# KNoT_Thing_Starter_Board.net
KiCad netlist of a schematic drawn in Altium Designer
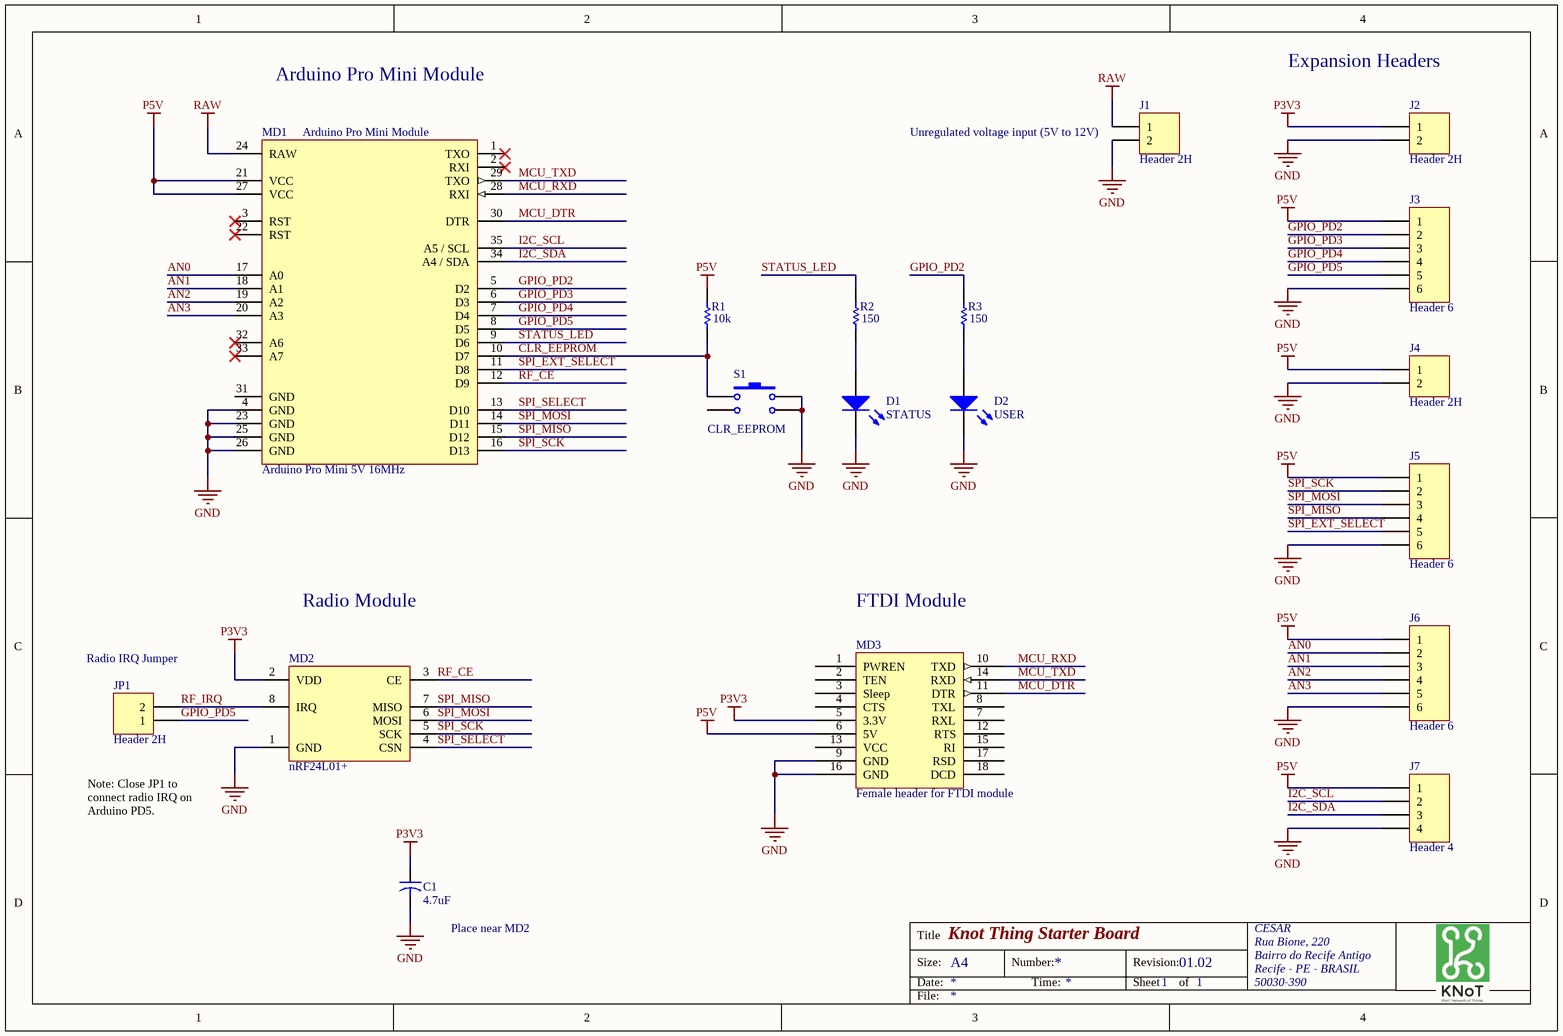
[diagram p0: KNoT_Thing_Starter_Board.SchDoc]

(export (version "E")
  (design (tool "Eeschema 10.0.6"))
  (components
    (comp (ref "C1")
      (value "4.7uF")
      (footprint "CAP RADIAL 5mm")
      (description "Capacitor Radial 4.7µF")
      (fields (field (name "Comment") "CAPC_RADIAL_100") (field (name "PUBLISHER") "Altium Limited"))
      (libsource (lib "KNoT_Thing") (part "CAPC1608L_1"))
    )
    (comp (ref "D1")
      (value "STATUS")
      (footprint "LED")
      (description "Typical RED, GREEN, YELLOW, AMBER GaAs LED")
      (fields (field (name "PUBLISHER") "Altium Limited"))
      (libsource (lib "KNoT_Thing") (part "LED"))
    )
    (comp (ref "D2")
      (value "USER")
      (footprint "LED")
      (description "Typical RED, GREEN, YELLOW, AMBER GaAs LED")
      (fields (field (name "PUBLISHER") "Altium Limited"))
      (libsource (lib "KNoT_Thing") (part "LED"))
    )
    (comp (ref "J1")
      (value "Header 2H")
      (footprint "HDR1X2")
      (description "Header, 2-Pin, Right Angle")
      (fields (field (name "PUBLISHER") "Altium Limited"))
      (libsource (lib "KNoT_Thing") (part "Header 2H"))
    )
    (comp (ref "J2")
      (value "Header 2H")
      (footprint "HDR1X2")
      (description "Header, 2-Pin, Right Angle")
      (fields (field (name "PUBLISHER") "Altium Limited"))
      (libsource (lib "KNoT_Thing") (part "Header 2H"))
    )
    (comp (ref "J3")
      (value "Header 6")
      (footprint "HDR1X6")
      (description "Header, 6-Pin")
      (fields (field (name "PUBLISHER") "Altium Limited"))
      (libsource (lib "KNoT_Thing") (part "Header 6"))
    )
    (comp (ref "J4")
      (value "Header 2H")
      (footprint "HDR1X2")
      (description "Header, 2-Pin, Right Angle")
      (fields (field (name "PUBLISHER") "Altium Limited"))
      (libsource (lib "KNoT_Thing") (part "Header 2H"))
    )
    (comp (ref "J5")
      (value "Header 6")
      (footprint "HDR1X6")
      (description "Header, 6-Pin")
      (fields (field (name "PUBLISHER") "Altium Limited"))
      (libsource (lib "KNoT_Thing") (part "Header 6"))
    )
    (comp (ref "J6")
      (value "Header 6")
      (footprint "HDR1X6")
      (description "Header, 6-Pin")
      (fields (field (name "PUBLISHER") "Altium Limited"))
      (libsource (lib "KNoT_Thing") (part "Header 6"))
    )
    (comp (ref "J7")
      (value "Header 4")
      (footprint "HDR1X4")
      (description "Header, 4-Pin")
      (fields (field (name "PUBLISHER") "Altium Limited"))
      (libsource (lib "KNoT_Thing") (part "Header 4"))
    )
    (comp (ref "JP1")
      (value "Header 2H")
      (footprint "HDR1X2")
      (description "Header, 2-Pin, Right Angle")
      (fields (field (name "PUBLISHER") "Altium Limited"))
      (libsource (lib "") (part "Header 2H_1"))
    )
    (comp (ref "MD1")
      (value "Arduino Pro Mini 5V 16MHz")
      (footprint "Arduino Pro Mini")
      (libsource (lib "KNoT_Thing") (part "Arduino Pro Mini 5V 16MHz"))
    )
    (comp (ref "MD2")
      (value "nRF24L01+")
      (footprint "nRF24L01+ Module")
      (description "2x4 Female Header Conector")
      (libsource (lib "KNoT_Thing") (part "nRF24L01+ Module"))
    )
    (comp (ref "MD3")
      (value "Female header for FTDI module")
      (footprint "FTDI_Module")
      (description "Connection header for custom FTDI module")
      (libsource (lib "KNoT_Thing") (part "Module_FTDI"))
    )
    (comp (ref "R1")
      (value "10k")
      (footprint "AXIAL-3mm")
      (description "Resistor")
      (fields (field (name "Comment") "Res1") (field (name "PUBLISHER") "Altium Limited"))
      (libsource (lib "KNoT_Thing") (part "Res1"))
    )
    (comp (ref "R2")
      (value "150")
      (footprint "AXIAL-3mm")
      (description "Resistor")
      (fields (field (name "Comment") "Res1") (field (name "PUBLISHER") "Altium Limited"))
      (libsource (lib "KNoT_Thing") (part "Res1"))
    )
    (comp (ref "R3")
      (value "150")
      (footprint "AXIAL-3mm")
      (description "Resistor")
      (fields (field (name "Comment") "Res1") (field (name "PUBLISHER") "Altium Limited"))
      (libsource (lib "KNoT_Thing") (part "Res1"))
    )
    (comp (ref "S1")
      (value "CLR_EEPROM")
      (footprint "SW-TACT")
      (description "B3F-1002 SWITCH TACT 6MM MOM 150GF")
      (fields (field (name "PUBLISHER") "Altium Limited"))
      (libsource (lib "KNoT_Thing") (part "SW-PB"))
    )
  )
  (nets
    (net (code "1") (name "/AN0") (class "Default")
      (node (ref "J6") (pin "2") (pinfunction "2_2") (pintype "passive"))
      (node (ref "MD1") (pin "17") (pinfunction "A0_17") (pintype "passive"))
    )
    (net (code "2") (name "/AN1") (class "Default")
      (node (ref "J6") (pin "3") (pinfunction "3_3") (pintype "passive"))
      (node (ref "MD1") (pin "18") (pinfunction "A1_18") (pintype "passive"))
    )
    (net (code "3") (name "/AN2") (class "Default")
      (node (ref "J6") (pin "4") (pinfunction "4_4") (pintype "passive"))
      (node (ref "MD1") (pin "19") (pinfunction "A2_19") (pintype "passive"))
    )
    (net (code "4") (name "/AN3") (class "Default")
      (node (ref "J6") (pin "5") (pinfunction "5_5") (pintype "passive"))
      (node (ref "MD1") (pin "20") (pinfunction "A3_20") (pintype "passive"))
    )
    (net (code "5") (name "/CLR_EEPROM") (class "Default")
      (node (ref "MD1") (pin "10") (pinfunction "D7_10") (pintype "passive"))
      (node (ref "R1") (pin "2") (pinfunction "2_2") (pintype "passive"))
      (node (ref "S1") (pin "1") (pinfunction "1_1") (pintype "passive"))
    )
    (net (code "6") (name "/GPIO_PD2") (class "Default")
      (node (ref "J3") (pin "2") (pinfunction "2_2") (pintype "passive"))
      (node (ref "MD1") (pin "5") (pinfunction "D2_5") (pintype "passive"))
      (node (ref "R3") (pin "1") (pinfunction "1_1") (pintype "passive"))
    )
    (net (code "7") (name "/GPIO_PD3") (class "Default")
      (node (ref "J3") (pin "3") (pinfunction "3_3") (pintype "passive"))
      (node (ref "MD1") (pin "6") (pinfunction "D3_6") (pintype "passive"))
    )
    (net (code "8") (name "/GPIO_PD4") (class "Default")
      (node (ref "J3") (pin "4") (pinfunction "4_4") (pintype "passive"))
      (node (ref "MD1") (pin "7") (pinfunction "D4_7") (pintype "passive"))
    )
    (net (code "9") (name "/GPIO_PD5") (class "Default")
      (node (ref "J3") (pin "5") (pinfunction "5_5") (pintype "passive"))
      (node (ref "JP1") (pin "1") (pinfunction "1_1") (pintype "passive"))
      (node (ref "MD1") (pin "8") (pinfunction "D5_8") (pintype "passive"))
    )
    (net (code "10") (name "/I2C_SCL") (class "Default")
      (node (ref "J7") (pin "2") (pinfunction "2_2") (pintype "passive"))
      (node (ref "MD1") (pin "35") (pinfunction "A5_/_SCL_35") (pintype "passive"))
    )
    (net (code "11") (name "/I2C_SDA") (class "Default")
      (node (ref "J7") (pin "3") (pinfunction "3_3") (pintype "passive"))
      (node (ref "MD1") (pin "34") (pinfunction "A4_/_SDA_34") (pintype "passive"))
    )
    (net (code "12") (name "/MCU_DTR") (class "Default")
      (node (ref "MD1") (pin "30") (pinfunction "DTR_30") (pintype "passive"))
      (node (ref "MD3") (pin "11") (pinfunction "DTR_11") (pintype "output"))
    )
    (net (code "13") (name "/MCU_RXD") (class "Default")
      (node (ref "MD1") (pin "28") (pinfunction "RXI_28") (pintype "input"))
      (node (ref "MD3") (pin "10") (pinfunction "TXD_10") (pintype "output"))
    )
    (net (code "14") (name "/MCU_TXD") (class "Default")
      (node (ref "MD1") (pin "29") (pinfunction "TXO_29") (pintype "output"))
      (node (ref "MD3") (pin "14") (pinfunction "RXD_14") (pintype "input"))
    )
    (net (code "15") (name "/RF_CE") (class "Default")
      (node (ref "MD1") (pin "12") (pinfunction "D9_12") (pintype "passive"))
      (node (ref "MD2") (pin "3") (pinfunction "CE_3") (pintype "passive"))
    )
    (net (code "16") (name "/RF_IRQ") (class "Default")
      (node (ref "JP1") (pin "2") (pinfunction "2_2") (pintype "passive"))
      (node (ref "MD2") (pin "8") (pinfunction "IRQ_8") (pintype "passive"))
    )
    (net (code "17") (name "/SPI_EXT_SELECT") (class "Default")
      (node (ref "J5") (pin "5") (pinfunction "5_5") (pintype "passive"))
      (node (ref "MD1") (pin "11") (pinfunction "D8_11") (pintype "passive"))
    )
    (net (code "18") (name "/SPI_MISO") (class "Default")
      (node (ref "J5") (pin "4") (pinfunction "4_4") (pintype "passive"))
      (node (ref "MD1") (pin "15") (pinfunction "D12_15") (pintype "passive"))
      (node (ref "MD2") (pin "7") (pinfunction "MISO_7") (pintype "passive"))
    )
    (net (code "19") (name "/SPI_MOSI") (class "Default")
      (node (ref "J5") (pin "3") (pinfunction "3_3") (pintype "passive"))
      (node (ref "MD1") (pin "14") (pinfunction "D11_14") (pintype "passive"))
      (node (ref "MD2") (pin "6") (pinfunction "MOSI_6") (pintype "passive"))
    )
    (net (code "20") (name "/SPI_SCK") (class "Default")
      (node (ref "J5") (pin "2") (pinfunction "2_2") (pintype "passive"))
      (node (ref "MD1") (pin "16") (pinfunction "D13_16") (pintype "passive"))
      (node (ref "MD2") (pin "5") (pinfunction "SCK_5") (pintype "passive"))
    )
    (net (code "21") (name "/SPI_SELECT") (class "Default")
      (node (ref "MD1") (pin "13") (pinfunction "D10_13") (pintype "passive"))
      (node (ref "MD2") (pin "4") (pinfunction "CSN_4") (pintype "passive"))
    )
    (net (code "22") (name "/STATUS_LED") (class "Default")
      (node (ref "MD1") (pin "9") (pinfunction "D6_9") (pintype "passive"))
      (node (ref "R2") (pin "1") (pinfunction "1_1") (pintype "passive"))
    )
    (net (code "23") (name "GND") (class "Default")
      (node (ref "C1") (pin "2") (pinfunction "2_2") (pintype "passive"))
      (node (ref "D1") (pin "2") (pinfunction "K_2") (pintype "passive"))
      (node (ref "D2") (pin "2") (pinfunction "K_2") (pintype "passive"))
      (node (ref "J1") (pin "2") (pinfunction "2_2") (pintype "passive"))
      (node (ref "J2") (pin "2") (pinfunction "2_2") (pintype "passive"))
      (node (ref "J3") (pin "6") (pinfunction "6_6") (pintype "passive"))
      (node (ref "J4") (pin "2") (pinfunction "2_2") (pintype "passive"))
      (node (ref "J5") (pin "6") (pinfunction "6_6") (pintype "passive"))
      (node (ref "J6") (pin "6") (pinfunction "6_6") (pintype "passive"))
      (node (ref "J7") (pin "4") (pinfunction "4_4") (pintype "passive"))
      (node (ref "MD1") (pin "23") (pinfunction "GND_23") (pintype "passive"))
      (node (ref "MD1") (pin "25") (pinfunction "GND_25") (pintype "passive"))
      (node (ref "MD1") (pin "26") (pinfunction "GND_26") (pintype "passive"))
      (node (ref "MD1") (pin "4") (pinfunction "GND_4") (pintype "passive"))
      (node (ref "MD2") (pin "1") (pinfunction "GND_1") (pintype "passive"))
      (node (ref "MD3") (pin "16") (pinfunction "GND_16") (pintype "passive"))
      (node (ref "MD3") (pin "9") (pinfunction "GND_9") (pintype "passive"))
      (node (ref "S1") (pin "3") (pinfunction "3_3") (pintype "passive"))
      (node (ref "S1") (pin "4") (pinfunction "4_4") (pintype "passive"))
    )
    (net (code "24") (name "Net-(D1-A)") (class "Default")
      (node (ref "D1") (pin "1") (pinfunction "A_1") (pintype "passive"))
      (node (ref "R2") (pin "2") (pinfunction "2_2") (pintype "passive"))
    )
    (net (code "25") (name "Net-(D2-A)") (class "Default")
      (node (ref "D2") (pin "1") (pinfunction "A_1") (pintype "passive"))
      (node (ref "R3") (pin "2") (pinfunction "2_2") (pintype "passive"))
    )
    (net (code "26") (name "P3V3") (class "Default")
      (node (ref "C1") (pin "1") (pinfunction "1_1") (pintype "passive"))
      (node (ref "J2") (pin "1") (pinfunction "1_1") (pintype "passive"))
      (node (ref "MD2") (pin "2") (pinfunction "VDD_2") (pintype "passive"))
      (node (ref "MD3") (pin "5") (pinfunction "3.3V_5") (pintype "passive"))
    )
    (net (code "27") (name "P5V") (class "Default")
      (node (ref "J3") (pin "1") (pinfunction "1_1") (pintype "passive"))
      (node (ref "J4") (pin "1") (pinfunction "1_1") (pintype "passive"))
      (node (ref "J5") (pin "1") (pinfunction "1_1") (pintype "passive"))
      (node (ref "J6") (pin "1") (pinfunction "1_1") (pintype "passive"))
      (node (ref "J7") (pin "1") (pinfunction "1_1") (pintype "passive"))
      (node (ref "MD1") (pin "21") (pinfunction "VCC_21") (pintype "passive"))
      (node (ref "MD1") (pin "27") (pinfunction "VCC_27") (pintype "passive"))
      (node (ref "MD3") (pin "6") (pinfunction "5V_6") (pintype "passive"))
      (node (ref "R1") (pin "1") (pinfunction "1_1") (pintype "passive"))
    )
    (net (code "28") (name "RAW") (class "Default")
      (node (ref "J1") (pin "1") (pinfunction "1_1") (pintype "passive"))
      (node (ref "MD1") (pin "24") (pinfunction "RAW_24") (pintype "passive"))
    )
    (net (code "29") (name "unconnected-(MD1-A6-Pad32)") (class "Default")
      (node (ref "MD1") (pin "32") (pinfunction "A6_32") (pintype "passive+no_connect"))
    )
    (net (code "30") (name "unconnected-(MD1-A7-Pad33)") (class "Default")
      (node (ref "MD1") (pin "33") (pinfunction "A7_33") (pintype "passive+no_connect"))
    )
    (net (code "31") (name "unconnected-(MD1-GND-Pad31)") (class "Default")
      (node (ref "MD1") (pin "31") (pinfunction "GND_31") (pintype "passive"))
    )
    (net (code "32") (name "unconnected-(MD1-RST-Pad3)") (class "Default")
      (node (ref "MD1") (pin "3") (pinfunction "RST_3") (pintype "passive+no_connect"))
    )
    (net (code "33") (name "unconnected-(MD1-RST-Pad22)") (class "Default")
      (node (ref "MD1") (pin "22") (pinfunction "RST_22") (pintype "passive+no_connect"))
    )
    (net (code "34") (name "unconnected-(MD1-RXI-Pad2)") (class "Default")
      (node (ref "MD1") (pin "2") (pinfunction "RXI_2") (pintype "passive+no_connect"))
    )
    (net (code "35") (name "unconnected-(MD1-TXO-Pad1)") (class "Default")
      (node (ref "MD1") (pin "1") (pinfunction "TXO_1") (pintype "passive+no_connect"))
    )
    (net (code "36") (name "unconnected-(MD3-CTS-Pad4)") (class "Default")
      (node (ref "MD3") (pin "4") (pinfunction "CTS_4") (pintype "passive"))
    )
    (net (code "37") (name "unconnected-(MD3-DCD-Pad18)") (class "Default")
      (node (ref "MD3") (pin "18") (pinfunction "DCD_18") (pintype "passive"))
    )
    (net (code "38") (name "unconnected-(MD3-PWREN-Pad1)") (class "Default")
      (node (ref "MD3") (pin "1") (pinfunction "PWREN_1") (pintype "passive"))
    )
    (net (code "39") (name "unconnected-(MD3-RI-Pad15)") (class "Default")
      (node (ref "MD3") (pin "15") (pinfunction "RI_15") (pintype "passive"))
    )
    (net (code "40") (name "unconnected-(MD3-RSD-Pad17)") (class "Default")
      (node (ref "MD3") (pin "17") (pinfunction "RSD_17") (pintype "passive"))
    )
    (net (code "41") (name "unconnected-(MD3-RTS-Pad12)") (class "Default")
      (node (ref "MD3") (pin "12") (pinfunction "RTS_12") (pintype "passive"))
    )
    (net (code "42") (name "unconnected-(MD3-RXL-Pad7)") (class "Default")
      (node (ref "MD3") (pin "7") (pinfunction "RXL_7") (pintype "passive"))
    )
    (net (code "43") (name "unconnected-(MD3-Sleep-Pad3)") (class "Default")
      (node (ref "MD3") (pin "3") (pinfunction "Sleep_3") (pintype "passive"))
    )
    (net (code "44") (name "unconnected-(MD3-TEN-Pad2)") (class "Default")
      (node (ref "MD3") (pin "2") (pinfunction "TEN_2") (pintype "passive"))
    )
    (net (code "45") (name "unconnected-(MD3-TXL-Pad8)") (class "Default")
      (node (ref "MD3") (pin "8") (pinfunction "TXL_8") (pintype "passive"))
    )
    (net (code "46") (name "unconnected-(MD3-VCC-Pad13)") (class "Default")
      (node (ref "MD3") (pin "13") (pinfunction "VCC_13") (pintype "passive"))
    )
    (net (code "47") (name "unconnected-(S1-Pad2)") (class "Default")
      (node (ref "S1") (pin "2") (pinfunction "2_2") (pintype "passive"))
    )
  )
)
